# u_build_45w_ps.net
KiCad netlist of a schematic drawn in EAGLE
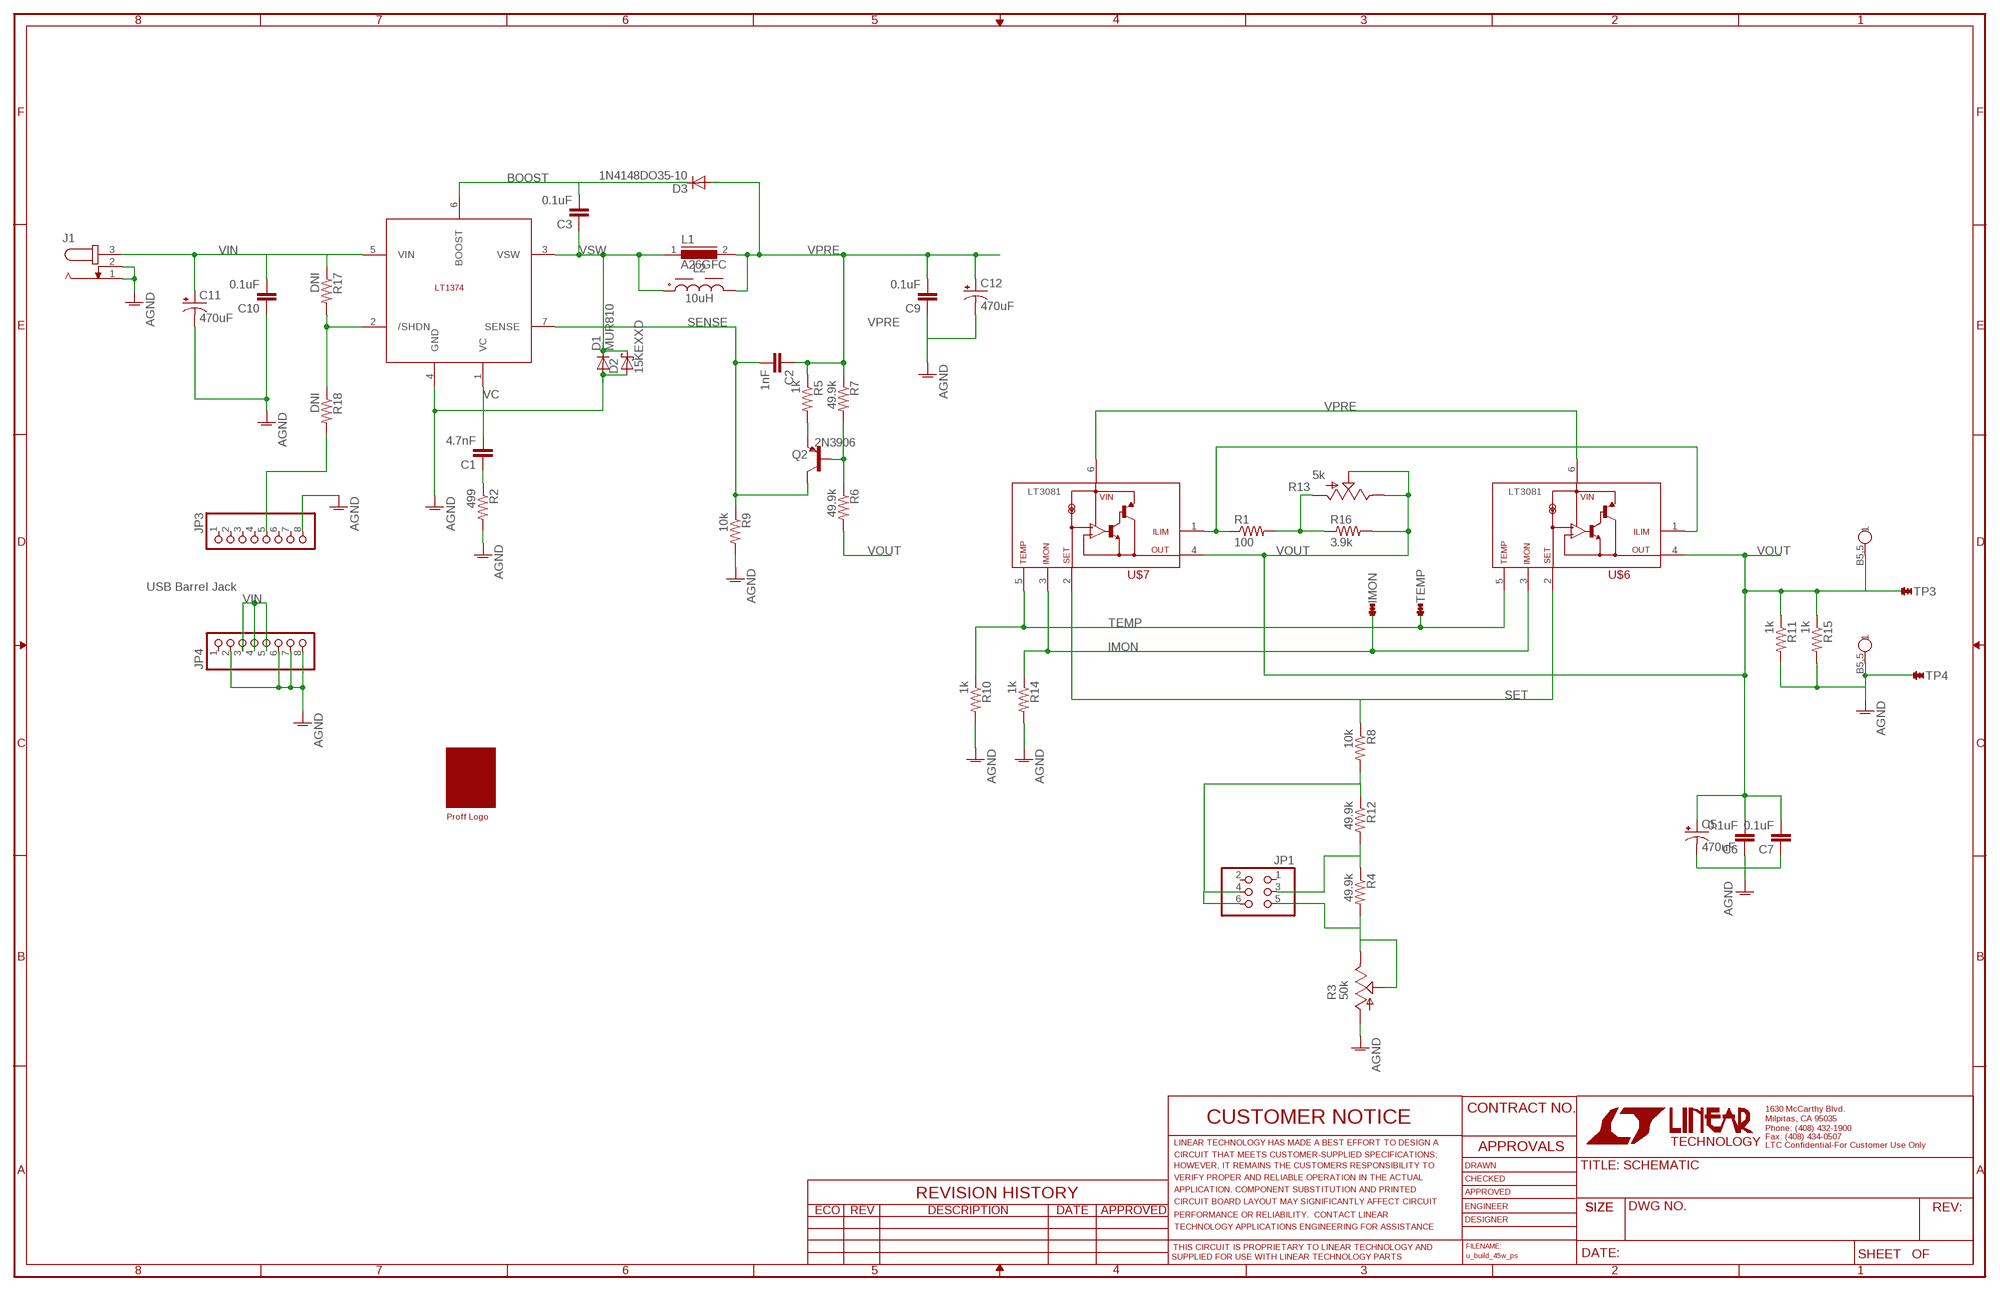
[diagram p0: schematic, sheet 1]

(export (version "E")
  (design (tool "Eeschema 10.0.6"))
  (components
    (comp (ref "C1")
      (value "4.7nF")
      (footprint "eagle-import:C050-025X075")
      (libsource (lib "eagle-import") (part "C-EU050-025X075"))
    )
    (comp (ref "C2")
      (value "1nF")
      (footprint "eagle-import:C050-025X075")
      (libsource (lib "eagle-import") (part "C-EU050-025X075"))
    )
    (comp (ref "C3")
      (value "0.1uF")
      (footprint "eagle-import:C050-025X075")
      (libsource (lib "eagle-import") (part "C-EU050-025X075"))
    )
    (comp (ref "C5")
      (value "470uF")
      (footprint "eagle-import:E5-10,5")
      (libsource (lib "eagle-import") (part "CPOL-USE5-10.5"))
    )
    (comp (ref "C6")
      (value "0.1uF")
      (footprint "eagle-import:C050-045X075")
      (libsource (lib "eagle-import") (part "C-EU050-045X075"))
    )
    (comp (ref "C7")
      (value "0.1uF")
      (footprint "eagle-import:C050-045X075")
      (libsource (lib "eagle-import") (part "C-EU050-045X075"))
    )
    (comp (ref "C9")
      (value "0.1uF")
      (footprint "eagle-import:C050-045X075")
      (libsource (lib "eagle-import") (part "C-EU050-045X075"))
    )
    (comp (ref "C10")
      (value "0.1uF")
      (footprint "eagle-import:C050-045X075")
      (libsource (lib "eagle-import") (part "C-EU050-045X075"))
    )
    (comp (ref "C11")
      (value "470uF")
      (footprint "eagle-import:E5-10,5")
      (libsource (lib "eagle-import") (part "CPOL-USE5-10.5"))
    )
    (comp (ref "C12")
      (value "470uF")
      (footprint "eagle-import:E5-10,5")
      (libsource (lib "eagle-import") (part "CPOL-USE5-10.5"))
    )
    (comp (ref "D1")
      (value "MUR810")
      (footprint "eagle-import:TO220ACS")
      (libsource (lib "eagle-import") (part "MUR810"))
    )
    (comp (ref "D2")
      (value "15KEXXD")
      (footprint "eagle-import:DO201T15")
      (libsource (lib "eagle-import") (part "15KEXXD"))
    )
    (comp (ref "D3")
      (value "1N4148DO35-10")
      (footprint "eagle-import:DO35-10")
      (libsource (lib "eagle-import") (part "1N4148DO35-10"))
    )
    (comp (ref "IC2")
      (value "LT1374TO220-7")
      (footprint "eagle-import:LT3081")
      (libsource (lib "eagle-import") (part "LT1374TO220-7"))
    )
    (comp (ref "IMON")
      (value "TURRET0.092")
      (footprint "eagle-import:TURRET_MILLMAX_2501-2")
      (libsource (lib "eagle-import") (part "TURRET0.092"))
    )
    (comp (ref "J1")
      (value "JACK-PLUG0")
      (footprint "eagle-import:SPC4077")
      (libsource (lib "eagle-import") (part "JACK-PLUG0"))
    )
    (comp (ref "J5")
      (value "BAN_JACK1")
      (footprint "eagle-import:PC_BAN_JACK")
      (libsource (lib "eagle-import") (part "BAN_JACK1"))
    )
    (comp (ref "J6")
      (value "BAN_JACK1")
      (footprint "eagle-import:PC_BAN_JACK")
      (libsource (lib "eagle-import") (part "BAN_JACK1"))
    )
    (comp (ref "JP1")
      (value "PINHD-2X3")
      (footprint "eagle-import:2X03")
      (libsource (lib "eagle-import") (part "PINHD-2X3"))
    )
    (comp (ref "JP3")
      (value "PINHD-1X8")
      (footprint "eagle-import:1X08")
      (libsource (lib "eagle-import") (part "PINHD-1X8"))
    )
    (comp (ref "JP4")
      (value "PINHD-1X8")
      (footprint "eagle-import:1X08")
      (libsource (lib "eagle-import") (part "PINHD-1X8"))
    )
    (comp (ref "L1")
      (value "A26GFC")
      (footprint "eagle-import:A26GFC")
      (libsource (lib "eagle-import") (part "A26GFC"))
    )
    (comp (ref "L2")
      (value "10uH")
      (footprint "eagle-import:WE-TIS_1111")
      (libsource (lib "eagle-import") (part "WE-TIS_1111_7447471100"))
    )
    (comp (ref "Q2")
      (value "2N3906")
      (footprint "eagle-import:TO92")
      (libsource (lib "eagle-import") (part "2N3906"))
    )
    (comp (ref "R1")
      (value "100")
      (footprint "eagle-import:0207_10")
      (libsource (lib "eagle-import") (part "R-US_0207/10"))
    )
    (comp (ref "R2")
      (value "499")
      (footprint "eagle-import:0207_10")
      (libsource (lib "eagle-import") (part "R-US_0207/10"))
    )
    (comp (ref "R3")
      (value "50k")
      (footprint "eagle-import:RS3")
      (libsource (lib "eagle-import") (part "TRIM_US-RS3"))
    )
    (comp (ref "R4")
      (value "49.9k")
      (footprint "eagle-import:0207_10")
      (libsource (lib "eagle-import") (part "R-US_0207/10"))
    )
    (comp (ref "R5")
      (value "1k")
      (footprint "eagle-import:0207_10")
      (libsource (lib "eagle-import") (part "R-US_0207/10"))
    )
    (comp (ref "R6")
      (value "49.9k")
      (footprint "eagle-import:0207_10")
      (libsource (lib "eagle-import") (part "R-US_0207/10"))
    )
    (comp (ref "R7")
      (value "49.9k")
      (footprint "eagle-import:0207_10")
      (libsource (lib "eagle-import") (part "R-US_0207/10"))
    )
    (comp (ref "R8")
      (value "10k")
      (footprint "eagle-import:0207_10")
      (libsource (lib "eagle-import") (part "R-US_0207/10"))
    )
    (comp (ref "R9")
      (value "10k")
      (footprint "eagle-import:0207_10")
      (libsource (lib "eagle-import") (part "R-US_0207/10"))
    )
    (comp (ref "R10")
      (value "1k")
      (footprint "eagle-import:0207_10")
      (libsource (lib "eagle-import") (part "R-US_0207/10"))
    )
    (comp (ref "R11")
      (value "1k")
      (footprint "eagle-import:0207_10")
      (libsource (lib "eagle-import") (part "R-US_0207/10"))
    )
    (comp (ref "R12")
      (value "49.9k")
      (footprint "eagle-import:0207_10")
      (libsource (lib "eagle-import") (part "R-US_0207/10"))
    )
    (comp (ref "R13")
      (value "5k")
      (footprint "eagle-import:RS3")
      (libsource (lib "eagle-import") (part "TRIM_US-RS3"))
    )
    (comp (ref "R14")
      (value "1k")
      (footprint "eagle-import:0207_10")
      (libsource (lib "eagle-import") (part "R-US_0207/10"))
    )
    (comp (ref "R15")
      (value "1k")
      (footprint "eagle-import:0207_10")
      (libsource (lib "eagle-import") (part "R-US_0207/10"))
    )
    (comp (ref "R16")
      (value "3.9k")
      (footprint "eagle-import:0207_10")
      (libsource (lib "eagle-import") (part "R-US_0207/10"))
    )
    (comp (ref "R17")
      (value "DNI")
      (footprint "eagle-import:0207_10")
      (libsource (lib "eagle-import") (part "R-US_0207/10"))
    )
    (comp (ref "R18")
      (value "DNI")
      (footprint "eagle-import:0207_10")
      (libsource (lib "eagle-import") (part "R-US_0207/10"))
    )
    (comp (ref "TEMP")
      (value "TURRET0.092")
      (footprint "eagle-import:TURRET_MILLMAX_2501-2")
      (libsource (lib "eagle-import") (part "TURRET0.092"))
    )
    (comp (ref "TP3")
      (value "TURRET0.092")
      (footprint "eagle-import:TURRET_MILLMAX_2501-2")
      (libsource (lib "eagle-import") (part "TURRET0.092"))
    )
    (comp (ref "TP4")
      (value "TURRET0.092")
      (footprint "eagle-import:TURRET_MILLMAX_2501-2")
      (libsource (lib "eagle-import") (part "TURRET0.092"))
    )
    (comp (ref "U$1")
      (value "PROFF")
      (footprint "eagle-import:PROFF")
      (libsource (lib "eagle-import") (part "PROFF"))
    )
    (comp (ref "U$6")
      (value "LT3081")
      (footprint "eagle-import:LT3081")
      (libsource (lib "eagle-import") (part "LT3081"))
    )
    (comp (ref "U$7")
      (value "LT3081")
      (footprint "eagle-import:LT3081")
      (libsource (lib "eagle-import") (part "LT3081"))
    )
  )
  (nets
    (net (code "1") (name "/BOOST") (class "Default")
      (node (ref "C3") (pin "2") (pinfunction "2_2") (pintype "passive"))
      (node (ref "D3") (pin "C") (pinfunction "C_C") (pintype "passive"))
      (node (ref "IC2") (pin "6") (pinfunction "BOOST_6") (pintype "bidirectional"))
    )
    (net (code "2") (name "/IMON") (class "Default")
      (node (ref "IMON") (pin "1") (pinfunction "1_1") (pintype "passive"))
      (node (ref "R14") (pin "1") (pinfunction "1_1") (pintype "passive"))
      (node (ref "U$6") (pin "3") (pinfunction "IMON_3") (pintype "bidirectional"))
      (node (ref "U$7") (pin "3") (pinfunction "IMON_3") (pintype "bidirectional"))
    )
    (net (code "3") (name "/SENSE") (class "Default")
      (node (ref "C2") (pin "2") (pinfunction "2_2") (pintype "passive"))
      (node (ref "IC2") (pin "7") (pinfunction "SENSE_7") (pintype "bidirectional"))
      (node (ref "Q2") (pin "1") (pinfunction "C_1") (pintype "passive"))
      (node (ref "R9") (pin "1") (pinfunction "1_1") (pintype "passive"))
    )
    (net (code "4") (name "/SET") (class "Default")
      (node (ref "R8") (pin "1") (pinfunction "1_1") (pintype "passive"))
      (node (ref "U$6") (pin "2") (pinfunction "SET_2") (pintype "bidirectional"))
      (node (ref "U$7") (pin "2") (pinfunction "SET_2") (pintype "bidirectional"))
    )
    (net (code "5") (name "/TEMP") (class "Default")
      (node (ref "R10") (pin "1") (pinfunction "1_1") (pintype "passive"))
      (node (ref "TEMP") (pin "1") (pinfunction "1_1") (pintype "passive"))
      (node (ref "U$6") (pin "5") (pinfunction "TEMP_5") (pintype "bidirectional"))
      (node (ref "U$7") (pin "5") (pinfunction "TEMP_5") (pintype "bidirectional"))
    )
    (net (code "6") (name "/VC") (class "Default")
      (node (ref "C1") (pin "2") (pinfunction "2_2") (pintype "passive"))
      (node (ref "IC2") (pin "1") (pinfunction "VC_1") (pintype "bidirectional"))
    )
    (net (code "7") (name "/VIN") (class "Default")
      (node (ref "C10") (pin "2") (pinfunction "2_2") (pintype "passive"))
      (node (ref "C11") (pin "+") (pinfunction "+_+") (pintype "passive"))
      (node (ref "IC2") (pin "5") (pinfunction "VIN_5") (pintype "bidirectional"))
      (node (ref "J1") (pin "3") (pinfunction "3_3") (pintype "passive"))
      (node (ref "JP4") (pin "3") (pinfunction "3_3") (pintype "passive"))
      (node (ref "JP4") (pin "4") (pinfunction "4_4") (pintype "passive"))
      (node (ref "JP4") (pin "5") (pinfunction "5_5") (pintype "passive"))
      (node (ref "R17") (pin "1") (pinfunction "1_1") (pintype "passive"))
    )
    (net (code "8") (name "/VOUT") (class "Default")
      (node (ref "C5") (pin "+") (pinfunction "+_+") (pintype "passive"))
      (node (ref "C6") (pin "2") (pinfunction "2_2") (pintype "passive"))
      (node (ref "C7") (pin "2") (pinfunction "2_2") (pintype "passive"))
      (node (ref "J5") (pin "B5,5") (pinfunction "1_B5,5") (pintype "passive"))
      (node (ref "R11") (pin "1") (pinfunction "1_1") (pintype "passive"))
      (node (ref "R13") (pin "E") (pinfunction "E_E") (pintype "passive"))
      (node (ref "R13") (pin "S") (pinfunction "S_S") (pintype "passive"))
      (node (ref "R15") (pin "1") (pinfunction "1_1") (pintype "passive"))
      (node (ref "R16") (pin "2") (pinfunction "2_2") (pintype "passive"))
      (node (ref "R6") (pin "2") (pinfunction "2_2") (pintype "passive"))
      (node (ref "TP3") (pin "1") (pinfunction "1_1") (pintype "passive"))
      (node (ref "U$6") (pin "4") (pinfunction "OUT_4") (pintype "bidirectional"))
      (node (ref "U$7") (pin "4") (pinfunction "OUT_4") (pintype "bidirectional"))
    )
    (net (code "9") (name "/VPRE") (class "Default")
      (node (ref "C12") (pin "+") (pinfunction "+_+") (pintype "passive"))
      (node (ref "C2") (pin "1") (pinfunction "1_1") (pintype "passive"))
      (node (ref "C9") (pin "2") (pinfunction "2_2") (pintype "passive"))
      (node (ref "D3") (pin "A") (pinfunction "A_A") (pintype "passive"))
      (node (ref "L1") (pin "2") (pinfunction "2_2") (pintype "passive"))
      (node (ref "L2") (pin "2") (pinfunction "2_2") (pintype "passive"))
      (node (ref "R5") (pin "1") (pinfunction "1_1") (pintype "passive"))
      (node (ref "R7") (pin "1") (pinfunction "1_1") (pintype "passive"))
      (node (ref "U$6") (pin "6") (pinfunction "VIN_6") (pintype "bidirectional"))
      (node (ref "U$7") (pin "6") (pinfunction "VIN_6") (pintype "bidirectional"))
    )
    (net (code "10") (name "/VSW") (class "Default")
      (node (ref "C3") (pin "1") (pinfunction "1_1") (pintype "passive"))
      (node (ref "D1") (pin "C") (pinfunction "C_C") (pintype "passive"))
      (node (ref "D2") (pin "C") (pinfunction "C_C") (pintype "passive"))
      (node (ref "IC2") (pin "3") (pinfunction "VSW_3") (pintype "bidirectional"))
      (node (ref "L1") (pin "1") (pinfunction "1_1") (pintype "passive"))
      (node (ref "L2") (pin "1") (pinfunction "1_1") (pintype "passive"))
    )
    (net (code "11") (name "AGND") (class "Default")
      (node (ref "C10") (pin "1") (pinfunction "1_1") (pintype "passive"))
      (node (ref "C11") (pin "-") (pinfunction "-_-") (pintype "passive"))
      (node (ref "C12") (pin "-") (pinfunction "-_-") (pintype "passive"))
      (node (ref "C5") (pin "-") (pinfunction "-_-") (pintype "passive"))
      (node (ref "C6") (pin "1") (pinfunction "1_1") (pintype "passive"))
      (node (ref "C7") (pin "1") (pinfunction "1_1") (pintype "passive"))
      (node (ref "C9") (pin "1") (pinfunction "1_1") (pintype "passive"))
      (node (ref "D1") (pin "A") (pinfunction "A_A") (pintype "passive"))
      (node (ref "D2") (pin "A") (pinfunction "A_A") (pintype "passive"))
      (node (ref "IC2") (pin "4") (pinfunction "GND_4") (pintype "bidirectional"))
      (node (ref "J1") (pin "1") (pinfunction "1_1") (pintype "passive"))
      (node (ref "J1") (pin "2") (pinfunction "2_2") (pintype "passive"))
      (node (ref "J6") (pin "B5,5") (pinfunction "1_B5,5") (pintype "passive"))
      (node (ref "JP3") (pin "8") (pinfunction "8_8") (pintype "passive"))
      (node (ref "JP4") (pin "2") (pinfunction "2_2") (pintype "passive"))
      (node (ref "JP4") (pin "6") (pinfunction "6_6") (pintype "passive"))
      (node (ref "JP4") (pin "7") (pinfunction "7_7") (pintype "passive"))
      (node (ref "JP4") (pin "8") (pinfunction "8_8") (pintype "passive"))
      (node (ref "R10") (pin "2") (pinfunction "2_2") (pintype "passive"))
      (node (ref "R11") (pin "2") (pinfunction "2_2") (pintype "passive"))
      (node (ref "R14") (pin "2") (pinfunction "2_2") (pintype "passive"))
      (node (ref "R15") (pin "2") (pinfunction "2_2") (pintype "passive"))
      (node (ref "R2") (pin "2") (pinfunction "2_2") (pintype "passive"))
      (node (ref "R3") (pin "A") (pinfunction "A_A") (pintype "passive"))
      (node (ref "R9") (pin "2") (pinfunction "2_2") (pintype "passive"))
      (node (ref "TP4") (pin "1") (pinfunction "1_1") (pintype "passive"))
    )
    (net (code "12") (name "Net-(C1-Pad1)") (class "Default")
      (node (ref "C1") (pin "1") (pinfunction "1_1") (pintype "passive"))
      (node (ref "R2") (pin "1") (pinfunction "1_1") (pintype "passive"))
    )
    (net (code "13") (name "Net-(IC2-{slash}SHDN)") (class "Default")
      (node (ref "IC2") (pin "2") (pinfunction "/SHDN_2") (pintype "bidirectional"))
      (node (ref "R17") (pin "2") (pinfunction "2_2") (pintype "passive"))
      (node (ref "R18") (pin "1") (pinfunction "1_1") (pintype "passive"))
    )
    (net (code "14") (name "Net-(JP1-Pad3)") (class "Default")
      (node (ref "JP1") (pin "3") (pinfunction "3_3") (pintype "passive"))
      (node (ref "R12") (pin "2") (pinfunction "2_2") (pintype "passive"))
      (node (ref "R4") (pin "1") (pinfunction "1_1") (pintype "passive"))
    )
    (net (code "15") (name "Net-(JP1-Pad4)") (class "Default")
      (node (ref "JP1") (pin "4") (pinfunction "4_4") (pintype "passive"))
      (node (ref "JP1") (pin "6") (pinfunction "6_6") (pintype "passive"))
      (node (ref "R12") (pin "1") (pinfunction "1_1") (pintype "passive"))
      (node (ref "R8") (pin "2") (pinfunction "2_2") (pintype "passive"))
    )
    (net (code "16") (name "Net-(JP1-Pad5)") (class "Default")
      (node (ref "JP1") (pin "5") (pinfunction "5_5") (pintype "passive"))
      (node (ref "R3") (pin "E") (pinfunction "E_E") (pintype "passive"))
      (node (ref "R3") (pin "S") (pinfunction "S_S") (pintype "passive"))
      (node (ref "R4") (pin "2") (pinfunction "2_2") (pintype "passive"))
    )
    (net (code "17") (name "Net-(JP3-Pad5)") (class "Default")
      (node (ref "JP3") (pin "5") (pinfunction "5_5") (pintype "passive"))
      (node (ref "R18") (pin "2") (pinfunction "2_2") (pintype "passive"))
    )
    (net (code "18") (name "Net-(Q2-B)") (class "Default")
      (node (ref "Q2") (pin "2") (pinfunction "B_2") (pintype "passive"))
      (node (ref "R6") (pin "1") (pinfunction "1_1") (pintype "passive"))
      (node (ref "R7") (pin "2") (pinfunction "2_2") (pintype "passive"))
    )
    (net (code "19") (name "Net-(Q2-E)") (class "Default")
      (node (ref "Q2") (pin "3") (pinfunction "E_3") (pintype "passive"))
      (node (ref "R5") (pin "2") (pinfunction "2_2") (pintype "passive"))
    )
    (net (code "20") (name "Net-(R1-Pad2)") (class "Default")
      (node (ref "R1") (pin "2") (pinfunction "2_2") (pintype "passive"))
      (node (ref "R13") (pin "A") (pinfunction "A_A") (pintype "passive"))
      (node (ref "R16") (pin "1") (pinfunction "1_1") (pintype "passive"))
    )
    (net (code "21") (name "Net-(U$6-ILIM)") (class "Default")
      (node (ref "R1") (pin "1") (pinfunction "1_1") (pintype "passive"))
      (node (ref "U$6") (pin "1") (pinfunction "ILIM_1") (pintype "bidirectional"))
      (node (ref "U$7") (pin "1") (pinfunction "ILIM_1") (pintype "bidirectional"))
    )
    (net (code "22") (name "unconnected-(JP1-Pad1)") (class "Default")
      (node (ref "JP1") (pin "1") (pinfunction "1_1") (pintype "passive"))
    )
    (net (code "23") (name "unconnected-(JP1-Pad2)") (class "Default")
      (node (ref "JP1") (pin "2") (pinfunction "2_2") (pintype "passive"))
    )
    (net (code "24") (name "unconnected-(JP3-Pad1)") (class "Default")
      (node (ref "JP3") (pin "1") (pinfunction "1_1") (pintype "passive"))
    )
    (net (code "25") (name "unconnected-(JP3-Pad2)") (class "Default")
      (node (ref "JP3") (pin "2") (pinfunction "2_2") (pintype "passive"))
    )
    (net (code "26") (name "unconnected-(JP3-Pad3)") (class "Default")
      (node (ref "JP3") (pin "3") (pinfunction "3_3") (pintype "passive"))
    )
    (net (code "27") (name "unconnected-(JP3-Pad4)") (class "Default")
      (node (ref "JP3") (pin "4") (pinfunction "4_4") (pintype "passive"))
    )
    (net (code "28") (name "unconnected-(JP3-Pad6)") (class "Default")
      (node (ref "JP3") (pin "6") (pinfunction "6_6") (pintype "passive"))
    )
    (net (code "29") (name "unconnected-(JP3-Pad7)") (class "Default")
      (node (ref "JP3") (pin "7") (pinfunction "7_7") (pintype "passive"))
    )
    (net (code "30") (name "unconnected-(JP4-Pad1)") (class "Default")
      (node (ref "JP4") (pin "1") (pinfunction "1_1") (pintype "passive"))
    )
  )
)
